# Converter_3V3-DDR4VCC.net
KiCad netlist of a schematic drawn in Altium Designer
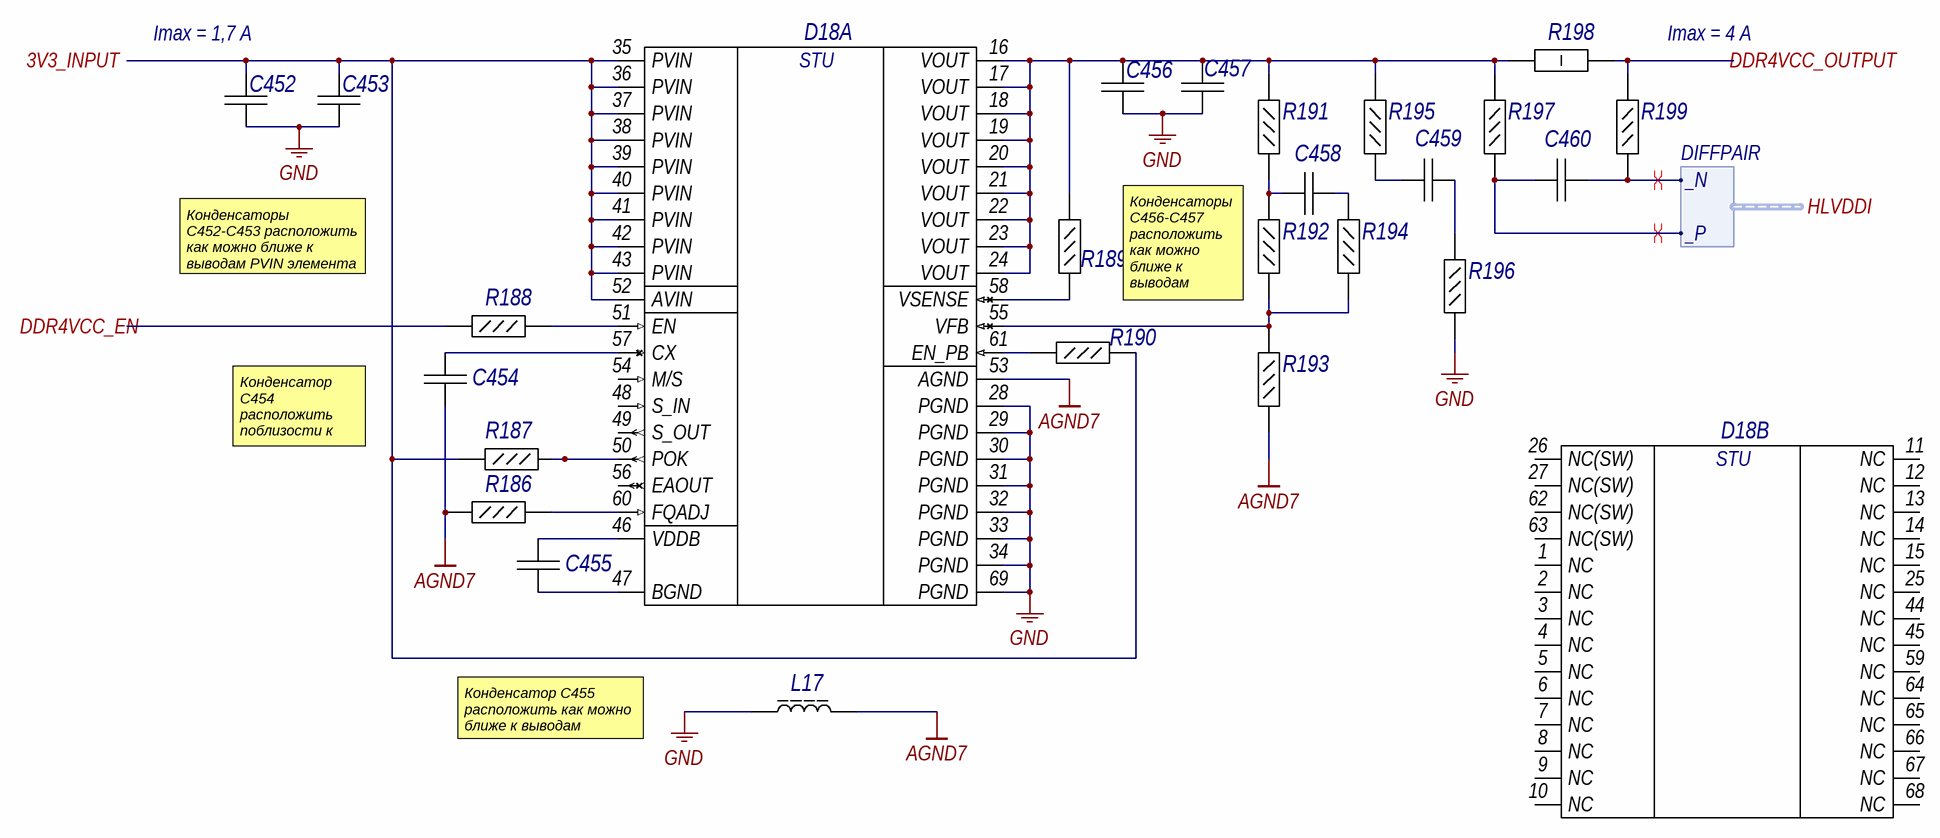
[diagram p0: Converter 3V3-DDR4VCC.SchDoc]

(export (version "E")
  (design (tool "Eeschema 10.0.6"))
  (components
    (comp (ref "C452")
      (value "GRM31CR61E226KE15L")
      (footprint "CAPC3216X180X55ML20T25")
      (description "Chip Capacitor, 22 uF, +/- 10%, 25 V, -55 to 85 degC, 1206 (3216 Metric), RoHS, Tape and Reel")
      (fields (field (name "TOLERANCE") "10%"))
      (libsource (lib "MiniPC DB") (part "CAP_NP"))
    )
    (comp (ref "C453")
      (value "GRM31CR61E226KE15L")
      (footprint "CAPC3216X180X55ML20T25")
      (description "Chip Capacitor, 22 uF, +/- 10%, 25 V, -55 to 85 degC, 1206 (3216 Metric), RoHS, Tape and Reel")
      (fields (field (name "TOLERANCE") "10%"))
      (libsource (lib "MiniPC DB") (part "CAP_NP"))
    )
    (comp (ref "C454")
      (value "VJ0402Y153JXQPW1BC")
      (footprint "CAPC1005X55X23ML05T8")
      (description "Chip Capacitor, 15 nF, +/- 5%, 10 V, -55 to 125 degC, 0402 (1005 Metric), RoHS, Tape and Reel")
      (fields (field (name "TOLERANCE") "5%"))
      (libsource (lib "MiniPC DB") (part "CAP_NP"))
    )
    (comp (ref "C455")
      (value "GRM155R61A224KE19D")
      (footprint "CAPC1005X55X25NL05T10")
      (description "Chip Capacitor, 220 nF, +/- 10%, 10 V, -55 to 85 degC, 0402 (1005 Metric), RoHS, Tape and Reel")
      (fields (field (name "TOLERANCE") "10%") (field (name "MANUFACTURER") "Basic Passives"))
      (libsource (lib "MiniPC DB") (part "CAP_NP"))
    )
    (comp (ref "C456")
      (value "C3216X5R1A476M160AB")
      (footprint "CAPC3216X180X20ML20")
      (description "Chip Capacitor, 47 uF, +/- 20%, 10 V, -55 to 85 degC, 1206 (3216 Metric), RoHS, Tape and Reel")
      (fields (field (name "TOLERANCE") "20%"))
      (libsource (lib "MiniPC DB") (part "CAP_NP"))
    )
    (comp (ref "C457")
      (value "C3216X5R1A476M160AB")
      (footprint "CAPC3216X180X20ML20")
      (description "Chip Capacitor, 47 uF, +/- 20%, 10 V, -55 to 85 degC, 1206 (3216 Metric), RoHS, Tape and Reel")
      (fields (field (name "TOLERANCE") "20%"))
      (libsource (lib "MiniPC DB") (part "CAP_NP"))
    )
    (comp (ref "C458")
      (value "C1005C0G1H220J050BA")
      (footprint "CAPC1005X55X10LL05")
      (description "Chip Capacitor, 22 pF, +/- 5%, 50 V, -55 to 125 degC, 0402 (1005 Metric), RoHS, Tape and Reel")
      (fields (field (name "TOLERANCE") "5%"))
      (libsource (lib "MiniPC DB") (part "CAP_NP"))
    )
    (comp (ref "C459")
      (value "GRM155R61A224KE19D")
      (footprint "CAPC1005X55X25NL05T10")
      (description "Chip Capacitor, 220 nF, +/- 10%, 10 V, -55 to 85 degC, 0402 (1005 Metric), RoHS, Tape and Reel")
      (fields (field (name "TOLERANCE") "10%") (field (name "MANUFACTURER") "Basic Passives"))
      (libsource (lib "MiniPC DB") (part "CAP_NP"))
    )
    (comp (ref "C460")
      (value "CGB2A1X5R1E105K033BC")
      (footprint "CAPC1005X33X10LL5")
      (description "Chip Capacitor, 1 uF, +/- 10%, 25 V, -55 to 85 degC, 0402 (1005 Metric), RoHS, Tape and Reel")
      (fields (field (name "TOLERANCE") "10%"))
      (libsource (lib "MiniPC DB") (part "CAP_NP"))
    )
    (comp (ref "D18")
      (value "EN6360QI")
      (footprint "ALTR-QFN-68_A-305_V")
      (libsource (lib "MiniPC DB") (part "EN6360QI"))
    )
    (comp (ref "L17")
      (value "742792609")
      (footprint "SMD-0603")
      (description "SMD EMI Suppression Ferrite Bead WE-CBF, Z = 30 Ohm")
      (libsource (lib "MiniPC DB") (part "Choke"))
    )
    (comp (ref "R186")
      (value "ERJ-2RKF5491X")
      (footprint "RESC1005X40X25LL05T05")
      (description "Chip Resistor, 5.49 KOhm, +/- 1%, 100 mW, -55 to 155 degC, 0402 (1005 Metric), RoHS, Tape and Reel")
      (fields (field (name "TOLERANCE") "1%") (field (name "MANUFACTURER") "Basic Passives"))
      (libsource (lib "") (part "RES-0.05_1"))
    )
    (comp (ref "R187")
      (value "ERJ-2RKF1003X")
      (footprint "RESC1005X40X25LL05T05")
      (description "Chip Resistor, 100 KOhm, +/- 1%, 100 mW, -55 to 155 degC, 0402 (1005 Metric), RoHS, Tape and Reel")
      (fields (field (name "TOLERANCE") "1%") (field (name "MANUFACTURER") "Basic Passives"))
      (libsource (lib "") (part "RES-0.05_1"))
    )
    (comp (ref "R188")
      (value "ERJ-2GE0R00X")
      (footprint "RESC1005X40X25LL05T05")
      (description "Chip Resistor, 0 mOhm, +/- 5%, 100 mW, -55 to 155 degC, 0402 (1005 Metric), RoHS, Tape and Reel")
      (fields (field (name "TOLERANCE") "5%") (field (name "MANUFACTURER") "Basic Passives"))
      (libsource (lib "") (part "RES-0.05_1"))
    )
    (comp (ref "R189")
      (value "ERJ-2GE0R00X")
      (footprint "RESC1005X40X25LL05T05")
      (description "Chip Resistor, 0 mOhm, +/- 5%, 100 mW, -55 to 155 degC, 0402 (1005 Metric), RoHS, Tape and Reel")
      (fields (field (name "TOLERANCE") "5%") (field (name "MANUFACTURER") "Basic Passives"))
      (libsource (lib "") (part "RES-0.05_2"))
    )
    (comp (ref "R190")
      (value "ERJ-2RKF1002X")
      (footprint "RESC1005X40X25LL05T05")
      (description "Chip Resistor, 10 KOhm, +/- 1%, 100 mW, -55 to 155 degC, 0402 (1005 Metric), RoHS, Tape and Reel")
      (fields (field (name "TOLERANCE") "1%") (field (name "MANUFACTURER") "Basic Passives"))
      (libsource (lib "") (part "RES-0.05_1"))
    )
    (comp (ref "R191")
      (value "ERJ-2GE0R00X")
      (footprint "RESC1005X40X25LL05T05")
      (description "Chip Resistor, 0 mOhm, +/- 5%, 100 mW, -55 to 155 degC, 0402 (1005 Metric), RoHS, Tape and Reel")
      (fields (field (name "TOLERANCE") "5%") (field (name "MANUFACTURER") "Basic Passives"))
      (libsource (lib "MiniPC DB") (part "RES-0.05"))
    )
    (comp (ref "R192")
      (value "CRCW0402160KFKED")
      (footprint "RESC1005X40X25LL05T05")
      (description "Chip Resistor, 160 KOhm, +/- 1%, 63 mW, -55 to 155 degC, 0402 (1005 Metric), RoHS, Tape and Reel")
      (fields (field (name "TOLERANCE") "1%") (field (name "MANUFACTURER") "Basic Passives"))
      (libsource (lib "MiniPC DB") (part "RES-0.05"))
    )
    (comp (ref "R193")
      (value "CRCW0402191KFKED")
      (footprint "RESC1005X40X25LL05T05")
      (description "Chip Resistor, 191 KOhm, +/- 1%, 63 mW, -55 to 155 degC, 0402 (1005 Metric), RoHS, Tape and Reel")
      (fields (field (name "TOLERANCE") "1%") (field (name "MANUFACTURER") "Basic Passives"))
      (libsource (lib "") (part "RES-0.05_2"))
    )
    (comp (ref "R194")
      (value "ERJ-2RKF1502X")
      (footprint "RESC1005X40X25LL05T05")
      (description "Chip Resistor, 15 KOhm, +/- 1%, 100 mW, -55 to 155 degC, 0402 (1005 Metric), RoHS, Tape and Reel")
      (fields (field (name "TOLERANCE") "1%") (field (name "MANUFACTURER") "Basic Passives"))
      (libsource (lib "MiniPC DB") (part "RES-0.05"))
    )
    (comp (ref "R195")
      (value "ERJ-2RKF1000X")
      (footprint "RESC1005X40X25LL05T05")
      (description "Chip Resistor, 100 Ohm, +/- 1%, 100 mW, -55 to 155 degC, 0402 (1005 Metric), RoHS, Tape and Reel")
      (fields (field (name "TOLERANCE") "1%") (field (name "MANUFACTURER") "Basic Passives"))
      (libsource (lib "MiniPC DB") (part "RES-0.05"))
    )
    (comp (ref "R196")
      (value "ERJ-2RKF1000X")
      (footprint "RESC1005X40X25LL05T05")
      (description "Chip Resistor, 100 Ohm, +/- 1%, 100 mW, -55 to 155 degC, 0402 (1005 Metric), RoHS, Tape and Reel")
      (fields (field (name "TOLERANCE") "1%") (field (name "MANUFACTURER") "Basic Passives"))
      (libsource (lib "") (part "RES-0.05_2"))
    )
    (comp (ref "R197")
      (value "ERJ-2RKF1002X")
      (footprint "RESC1005X40X25LL05T05")
      (description "Chip Resistor, 10 KOhm, +/- 1%, 100 mW, -55 to 155 degC, 0402 (1005 Metric), RoHS, Tape and Reel")
      (fields (field (name "TOLERANCE") "1%") (field (name "MANUFACTURER") "Basic Passives"))
      (libsource (lib "") (part "RES-0.05_2"))
    )
    (comp (ref "R198")
      (value "WSLP12061L000FEA")
      (footprint "RESC3216X89X104LL25T25")
      (description "Chip Resistor, 0.001 Ohm, +/- 1%, 1 W, -65 to 170 degC, 1206 (3216 Metric), RoHS, Tape and Reel")
      (fields (field (name "TOLERANCE") "1%"))
      (libsource (lib "MiniPC DB") (part "RES-1"))
    )
    (comp (ref "R199")
      (value "ERJ-2RKF1002X")
      (footprint "RESC1005X40X25LL05T05")
      (description "Chip Resistor, 10 KOhm, +/- 1%, 100 mW, -55 to 155 degC, 0402 (1005 Metric), RoHS, Tape and Reel")
      (fields (field (name "TOLERANCE") "1%") (field (name "MANUFACTURER") "Basic Passives"))
      (libsource (lib "") (part "RES-0.05_2"))
    )
  )
  (nets
    (net (code "2") (name "/3V3_INPUT") (class "Default")
      (node (ref "C452") (pin "2") (pinfunction "2_2") (pintype "passive"))
      (node (ref "C453") (pin "2") (pinfunction "2_2") (pintype "passive"))
      (node (ref "D18") (pin "35") (pinfunction "PVIN_35") (pintype "power_in"))
      (node (ref "D18") (pin "36") (pinfunction "PVIN_36") (pintype "power_in"))
      (node (ref "D18") (pin "37") (pinfunction "PVIN_37") (pintype "power_in"))
      (node (ref "D18") (pin "38") (pinfunction "PVIN_38") (pintype "power_in"))
      (node (ref "D18") (pin "39") (pinfunction "PVIN_39") (pintype "power_in"))
      (node (ref "D18") (pin "40") (pinfunction "PVIN_40") (pintype "power_in"))
      (node (ref "D18") (pin "41") (pinfunction "PVIN_41") (pintype "power_in"))
      (node (ref "D18") (pin "42") (pinfunction "PVIN_42") (pintype "power_in"))
      (node (ref "D18") (pin "43") (pinfunction "PVIN_43") (pintype "power_in"))
      (node (ref "D18") (pin "52") (pinfunction "AVIN_52") (pintype "power_in"))
      (node (ref "R187") (pin "2") (pinfunction "2_2") (pintype "passive"))
      (node (ref "R190") (pin "1") (pinfunction "1_1") (pintype "passive"))
    )
    (net (code "3") (name "/DDR4VCC_EN") (class "Default")
      (node (ref "R188") (pin "2") (pinfunction "2_2") (pintype "passive"))
    )
    (net (code "4") (name "/DDR4VCC_OUTPUT") (class "Default")
      (node (ref "R198") (pin "1") (pinfunction "1_1") (pintype "passive"))
      (node (ref "R199") (pin "2") (pinfunction "2_2") (pintype "passive"))
    )
    (net (code "6") (name "AGND7") (class "Default")
      (node (ref "C454") (pin "1") (pinfunction "1_1") (pintype "passive"))
      (node (ref "D18") (pin "53") (pinfunction "AGND_53") (pintype "power_in"))
      (node (ref "L17") (pin "2") (pinfunction "2_2") (pintype "passive"))
      (node (ref "R186") (pin "2") (pinfunction "2_2") (pintype "passive"))
      (node (ref "R193") (pin "1") (pinfunction "1_1") (pintype "passive"))
    )
    (net (code "7") (name "GND") (class "Default")
      (node (ref "C452") (pin "1") (pinfunction "1_1") (pintype "passive"))
      (node (ref "C453") (pin "1") (pinfunction "1_1") (pintype "passive"))
      (node (ref "C456") (pin "1") (pinfunction "1_1") (pintype "passive"))
      (node (ref "C457") (pin "1") (pinfunction "1_1") (pintype "passive"))
      (node (ref "D18") (pin "28") (pinfunction "PGND_28") (pintype "power_in"))
      (node (ref "D18") (pin "29") (pinfunction "PGND_29") (pintype "power_in"))
      (node (ref "D18") (pin "30") (pinfunction "PGND_30") (pintype "power_in"))
      (node (ref "D18") (pin "31") (pinfunction "PGND_31") (pintype "power_in"))
      (node (ref "D18") (pin "32") (pinfunction "PGND_32") (pintype "power_in"))
      (node (ref "D18") (pin "33") (pinfunction "PGND_33") (pintype "power_in"))
      (node (ref "D18") (pin "34") (pinfunction "PGND_34") (pintype "power_in"))
      (node (ref "D18") (pin "69") (pinfunction "PGND_69") (pintype "power_in"))
      (node (ref "L17") (pin "1") (pinfunction "1_1") (pintype "passive"))
      (node (ref "R196") (pin "1") (pinfunction "1_1") (pintype "passive"))
    )
    (net (code "8") (name "Net-(C456-Pad2)") (class "Default")
      (node (ref "C456") (pin "2") (pinfunction "2_2") (pintype "passive"))
      (node (ref "C457") (pin "2") (pinfunction "2_2") (pintype "passive"))
      (node (ref "D18") (pin "16") (pinfunction "VOUT_16") (pintype "power_in"))
      (node (ref "D18") (pin "17") (pinfunction "VOUT_17") (pintype "power_in"))
      (node (ref "D18") (pin "18") (pinfunction "VOUT_18") (pintype "power_in"))
      (node (ref "D18") (pin "19") (pinfunction "VOUT_19") (pintype "power_in"))
      (node (ref "D18") (pin "20") (pinfunction "VOUT_20") (pintype "power_in"))
      (node (ref "D18") (pin "21") (pinfunction "VOUT_21") (pintype "power_in"))
      (node (ref "D18") (pin "22") (pinfunction "VOUT_22") (pintype "power_in"))
      (node (ref "D18") (pin "23") (pinfunction "VOUT_23") (pintype "power_in"))
      (node (ref "D18") (pin "24") (pinfunction "VOUT_24") (pintype "power_in"))
      (node (ref "R189") (pin "2") (pinfunction "2_2") (pintype "passive"))
      (node (ref "R191") (pin "1") (pinfunction "1_1") (pintype "passive"))
      (node (ref "R195") (pin "1") (pinfunction "1_1") (pintype "passive"))
      (node (ref "R197") (pin "2") (pinfunction "2_2") (pintype "passive"))
      (node (ref "R198") (pin "2") (pinfunction "2_2") (pintype "passive"))
    )
    (net (code "9") (name "Net-(C458-Pad1)") (class "Default")
      (node (ref "C458") (pin "1") (pinfunction "1_1") (pintype "passive"))
      (node (ref "R191") (pin "2") (pinfunction "2_2") (pintype "passive"))
      (node (ref "R192") (pin "1") (pinfunction "1_1") (pintype "passive"))
    )
    (net (code "10") (name "Net-(C458-Pad2)") (class "Default")
      (node (ref "C458") (pin "2") (pinfunction "2_2") (pintype "passive"))
      (node (ref "R194") (pin "1") (pinfunction "1_1") (pintype "passive"))
    )
    (net (code "11") (name "Net-(C459-Pad1)") (class "Default")
      (node (ref "C459") (pin "1") (pinfunction "1_1") (pintype "passive"))
      (node (ref "R195") (pin "2") (pinfunction "2_2") (pintype "passive"))
    )
    (net (code "12") (name "Net-(C459-Pad2)") (class "Default")
      (node (ref "C459") (pin "2") (pinfunction "2_2") (pintype "passive"))
      (node (ref "R196") (pin "2") (pinfunction "2_2") (pintype "passive"))
    )
    (net (code "13") (name "Net-(C460-Pad1)") (class "Default")
      (node (ref "C460") (pin "1") (pinfunction "1_1") (pintype "passive"))
      (node (ref "R199") (pin "1") (pinfunction "1_1") (pintype "passive"))
    )
    (net (code "14") (name "Net-(C460-Pad2)") (class "Default")
      (node (ref "C460") (pin "2") (pinfunction "2_2") (pintype "passive"))
      (node (ref "R197") (pin "1") (pinfunction "1_1") (pintype "passive"))
    )
    (net (code "15") (name "Net-(D18A-BGND)") (class "Default")
      (node (ref "C455") (pin "1") (pinfunction "1_1") (pintype "passive"))
      (node (ref "D18") (pin "47") (pinfunction "BGND_47") (pintype "power_in"))
    )
    (net (code "16") (name "Net-(D18A-CX)") (class "Default")
      (node (ref "C454") (pin "2") (pinfunction "2_2") (pintype "passive"))
      (node (ref "D18") (pin "57") (pinfunction "CX_57") (pintype "input"))
    )
    (net (code "17") (name "Net-(D18A-EN)") (class "Default")
      (node (ref "D18") (pin "51") (pinfunction "EN_51") (pintype "input"))
      (node (ref "R188") (pin "1") (pinfunction "1_1") (pintype "passive"))
    )
    (net (code "18") (name "Net-(D18A-EN_PB)") (class "Default")
      (node (ref "D18") (pin "61") (pinfunction "EN_PB_61") (pintype "input"))
      (node (ref "R190") (pin "2") (pinfunction "2_2") (pintype "passive"))
    )
    (net (code "19") (name "Net-(D18A-FQADJ)") (class "Default")
      (node (ref "D18") (pin "60") (pinfunction "FQADJ_60") (pintype "input"))
      (node (ref "R186") (pin "1") (pinfunction "1_1") (pintype "passive"))
    )
    (net (code "20") (name "Net-(D18A-POK)") (class "Default")
      (node (ref "D18") (pin "50") (pinfunction "POK_50") (pintype "output"))
      (node (ref "R187") (pin "1") (pinfunction "1_1") (pintype "passive"))
    )
    (net (code "21") (name "Net-(D18A-VDDB)") (class "Default")
      (node (ref "C455") (pin "2") (pinfunction "2_2") (pintype "passive"))
      (node (ref "D18") (pin "46") (pinfunction "VDDB_46") (pintype "power_in"))
    )
    (net (code "22") (name "Net-(D18A-VFB)") (class "Default")
      (node (ref "D18") (pin "55") (pinfunction "VFB_55") (pintype "input"))
      (node (ref "R192") (pin "2") (pinfunction "2_2") (pintype "passive"))
      (node (ref "R193") (pin "2") (pinfunction "2_2") (pintype "passive"))
      (node (ref "R194") (pin "2") (pinfunction "2_2") (pintype "passive"))
    )
    (net (code "23") (name "Net-(D18A-VSENSE)") (class "Default")
      (node (ref "D18") (pin "58") (pinfunction "VSENSE_58") (pintype "input"))
      (node (ref "R189") (pin "1") (pinfunction "1_1") (pintype "passive"))
    )
    (net (code "24") (name "unconnected-(D18A-EAOUT-Pad56)") (class "Default")
      (node (ref "D18") (pin "56") (pinfunction "EAOUT_56") (pintype "output"))
    )
    (net (code "25") (name "unconnected-(D18A-M{slash}S-Pad54)") (class "Default")
      (node (ref "D18") (pin "54") (pinfunction "M/S_54") (pintype "input"))
    )
    (net (code "26") (name "unconnected-(D18A-S_IN-Pad48)") (class "Default")
      (node (ref "D18") (pin "48") (pinfunction "S_IN_48") (pintype "input"))
    )
    (net (code "27") (name "unconnected-(D18A-S_OUT-Pad49)") (class "Default")
      (node (ref "D18") (pin "49") (pinfunction "S_OUT_49") (pintype "output"))
    )
    (net (code "28") (name "unconnected-(D18B-NC(SW)-Pad26)") (class "Default")
      (node (ref "D18") (pin "26") (pinfunction "NC(SW)_26") (pintype "passive"))
    )
    (net (code "29") (name "unconnected-(D18B-NC(SW)-Pad27)") (class "Default")
      (node (ref "D18") (pin "27") (pinfunction "NC(SW)_27") (pintype "passive"))
    )
    (net (code "30") (name "unconnected-(D18B-NC(SW)-Pad62)") (class "Default")
      (node (ref "D18") (pin "62") (pinfunction "NC(SW)_62") (pintype "passive"))
    )
    (net (code "31") (name "unconnected-(D18B-NC(SW)-Pad63)") (class "Default")
      (node (ref "D18") (pin "63") (pinfunction "NC(SW)_63") (pintype "passive"))
    )
    (net (code "32") (name "unconnected-(D18B-NC-Pad1)") (class "Default")
      (node (ref "D18") (pin "1") (pinfunction "NC_1") (pintype "passive"))
    )
    (net (code "33") (name "unconnected-(D18B-NC-Pad2)") (class "Default")
      (node (ref "D18") (pin "2") (pinfunction "NC_2") (pintype "passive"))
    )
    (net (code "34") (name "unconnected-(D18B-NC-Pad3)") (class "Default")
      (node (ref "D18") (pin "3") (pinfunction "NC_3") (pintype "passive"))
    )
    (net (code "35") (name "unconnected-(D18B-NC-Pad4)") (class "Default")
      (node (ref "D18") (pin "4") (pinfunction "NC_4") (pintype "passive"))
    )
    (net (code "36") (name "unconnected-(D18B-NC-Pad5)") (class "Default")
      (node (ref "D18") (pin "5") (pinfunction "NC_5") (pintype "passive"))
    )
    (net (code "37") (name "unconnected-(D18B-NC-Pad6)") (class "Default")
      (node (ref "D18") (pin "6") (pinfunction "NC_6") (pintype "passive"))
    )
    (net (code "38") (name "unconnected-(D18B-NC-Pad7)") (class "Default")
      (node (ref "D18") (pin "7") (pinfunction "NC_7") (pintype "passive"))
    )
    (net (code "39") (name "unconnected-(D18B-NC-Pad8)") (class "Default")
      (node (ref "D18") (pin "8") (pinfunction "NC_8") (pintype "passive"))
    )
    (net (code "40") (name "unconnected-(D18B-NC-Pad9)") (class "Default")
      (node (ref "D18") (pin "9") (pinfunction "NC_9") (pintype "passive"))
    )
    (net (code "41") (name "unconnected-(D18B-NC-Pad10)") (class "Default")
      (node (ref "D18") (pin "10") (pinfunction "NC_10") (pintype "passive"))
    )
    (net (code "42") (name "unconnected-(D18B-NC-Pad11)") (class "Default")
      (node (ref "D18") (pin "11") (pinfunction "NC_11") (pintype "passive"))
    )
    (net (code "43") (name "unconnected-(D18B-NC-Pad12)") (class "Default")
      (node (ref "D18") (pin "12") (pinfunction "NC_12") (pintype "passive"))
    )
    (net (code "44") (name "unconnected-(D18B-NC-Pad13)") (class "Default")
      (node (ref "D18") (pin "13") (pinfunction "NC_13") (pintype "passive"))
    )
    (net (code "45") (name "unconnected-(D18B-NC-Pad14)") (class "Default")
      (node (ref "D18") (pin "14") (pinfunction "NC_14") (pintype "passive"))
    )
    (net (code "46") (name "unconnected-(D18B-NC-Pad15)") (class "Default")
      (node (ref "D18") (pin "15") (pinfunction "NC_15") (pintype "passive"))
    )
    (net (code "47") (name "unconnected-(D18B-NC-Pad25)") (class "Default")
      (node (ref "D18") (pin "25") (pinfunction "NC_25") (pintype "passive"))
    )
    (net (code "48") (name "unconnected-(D18B-NC-Pad44)") (class "Default")
      (node (ref "D18") (pin "44") (pinfunction "NC_44") (pintype "passive"))
    )
    (net (code "49") (name "unconnected-(D18B-NC-Pad45)") (class "Default")
      (node (ref "D18") (pin "45") (pinfunction "NC_45") (pintype "passive"))
    )
    (net (code "50") (name "unconnected-(D18B-NC-Pad59)") (class "Default")
      (node (ref "D18") (pin "59") (pinfunction "NC_59") (pintype "passive"))
    )
    (net (code "51") (name "unconnected-(D18B-NC-Pad64)") (class "Default")
      (node (ref "D18") (pin "64") (pinfunction "NC_64") (pintype "passive"))
    )
    (net (code "52") (name "unconnected-(D18B-NC-Pad65)") (class "Default")
      (node (ref "D18") (pin "65") (pinfunction "NC_65") (pintype "passive"))
    )
    (net (code "53") (name "unconnected-(D18B-NC-Pad66)") (class "Default")
      (node (ref "D18") (pin "66") (pinfunction "NC_66") (pintype "passive"))
    )
    (net (code "54") (name "unconnected-(D18B-NC-Pad67)") (class "Default")
      (node (ref "D18") (pin "67") (pinfunction "NC_67") (pintype "passive"))
    )
    (net (code "55") (name "unconnected-(D18B-NC-Pad68)") (class "Default")
      (node (ref "D18") (pin "68") (pinfunction "NC_68") (pintype "passive"))
    )
  )
)
